# AVCC.net
KiCad netlist of a schematic drawn in Altium Designer
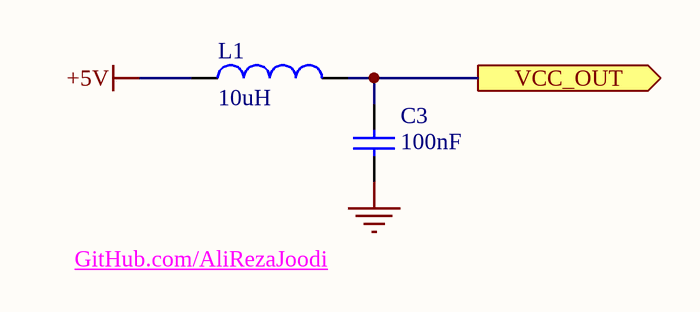
[diagram p0: AVCC.SchDoc]

(export (version "E")
  (design (tool "Eeschema 10.0.6"))
  (components
    (comp (ref "C3")
      (value "100nF")
      (footprint "CAPNTO2.54-3.05x1.78A")
      (description "Capacitor")
      (fields
        (field (name "MANUFACTURER") "Generic Components")
        (field (name "Comment") "Cap")
        (field (name "PUBLISHER") "Altium Limited")
      )
      (libsource (lib "Miscellaneous Devices") (part "Cap"))
    )
    (comp (ref "L1")
      (value "10uH")
      (footprint "Inductor_1")
      (description "Inductor")
      (fields (field (name "MANUFACTURER") "Generic Components") (field (name "PUBLISHER") "Altium Limited"))
      (libsource (lib "my Libraries") (part "Inductor"))
    )
  )
  (nets
    (net (code "1") (name "+5V") (class "Default")
      (node (ref "L1") (pin "1") (pinfunction "1_1") (pintype "passive"))
    )
    (net (code "2") (name "/VCC_OUT") (class "Default")
      (node (ref "C3") (pin "1") (pinfunction "1_1") (pintype "passive"))
      (node (ref "L1") (pin "2") (pinfunction "2_2") (pintype "passive"))
    )
    (net (code "3") (name "GND") (class "Default")
      (node (ref "C3") (pin "2") (pinfunction "2_2") (pintype "passive"))
    )
  )
)
